# 6_CLCD.net
KiCad netlist of a schematic drawn in Altium Designer
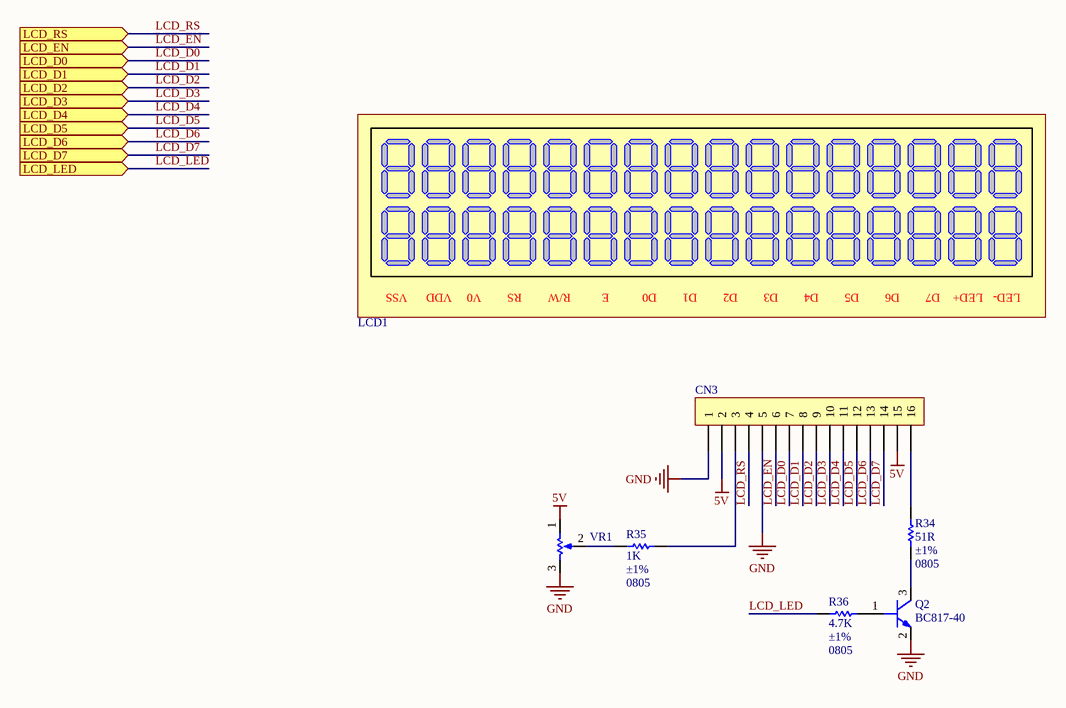
[diagram p0: 6.CLCD.SchDoc]

(export (version "E")
  (design (tool "Eeschema 10.0.6"))
  (components
    (comp (ref "CN3")
      (value "HDR_1X16")
      (footprint "HDRFV16W70P254_1X16_4064X254X1118P")
      (description "CONN HEADER FEMALE 16POS.1\" TIN")
      (fields
        (field (name "PART NUMBER") "SCON00136")
        (field (name "MANUFACTURER") "Sullins Connector Solutions")
      )
      (libsource (lib "ComponentDatabase") (part "HDR_1X16"))
    )
    (comp (ref "LCD1")
      (value "HD44780")
      (footprint "HD44780")
      (description "LCD MODULE 16X2 CHARACTER")
      (fields (field (name "PART NUMBER") "SOPT00201") (field (name "VOLTAGE") "5V"))
      (libsource (lib "ComponentDatabase") (part "HD44780"))
    )
    (comp (ref "Q2")
      (value "BC817-40")
      (footprint "SOT95P230X110-3N_SOT-23")
      (description "TRANS NPN 45V 0.5A SOT23")
      (fields (field (name "PART NUMBER") "STRANS00034") (field (name "MANUFACTURER") "NXP Semiconductors"))
      (libsource (lib "ComponentDatabase") (part "BC817"))
    )
    (comp (ref "R34")
      (value "51R")
      (footprint "RESC2013X65N_EIA0805")
      (description "RES SMD 51 OHM 1% 1/8W 0805")
      (fields
        (field (name "PART NUMBER") "SRES03010043")
        (field (name "TOLERANCE") "±1%")
        (field (name "PACKAGE / CASE") "0805")
        (field (name "MANUFACTURER") "Yageo")
      )
      (libsource (lib "ComponentDatabase") (part "RES"))
    )
    (comp (ref "R35")
      (value "1K")
      (footprint "RESC2013X65N_EIA0805")
      (description "RES SMD 1K OHM 1% 1/8W 0805")
      (fields
        (field (name "PART NUMBER") "SRES03010074")
        (field (name "TOLERANCE") "±1%")
        (field (name "PACKAGE / CASE") "0805")
        (field (name "MANUFACTURER") "Yageo")
      )
      (libsource (lib "ComponentDatabase") (part "RES"))
    )
    (comp (ref "R36")
      (value "4.7K")
      (footprint "RESC2013X65N_EIA0805")
      (description "RES SMD 4.7K OHM 1% 1/8W 0805")
      (fields
        (field (name "PART NUMBER") "SRES03010090")
        (field (name "TOLERANCE") "±1%")
        (field (name "PACKAGE / CASE") "0805")
        (field (name "MANUFACTURER") "Yageo")
      )
      (libsource (lib "ComponentDatabase") (part "RES"))
    )
    (comp (ref "VR1")
      (value "POT")
      (footprint "TRIMMER_SMD")
      (description "TRIMMER 10K OHM 0.15W SMD")
      (fields (field (name "PART NUMBER") "SPOT00047") (field (name "TOLERANCE") "±25%"))
      (libsource (lib "ComponentDatabase") (part "POT"))
    )
  )
  (nets
    (net (code "1") (name "/LCD_D0") (class "Default")
      (node (ref "CN3") (pin "7") (pinfunction "7_7") (pintype "passive"))
    )
    (net (code "2") (name "/LCD_D1") (class "Default")
      (node (ref "CN3") (pin "8") (pinfunction "8_8") (pintype "passive"))
    )
    (net (code "3") (name "/LCD_D2") (class "Default")
      (node (ref "CN3") (pin "9") (pinfunction "9_9") (pintype "passive"))
    )
    (net (code "4") (name "/LCD_D3") (class "Default")
      (node (ref "CN3") (pin "10") (pinfunction "10_10") (pintype "passive"))
    )
    (net (code "5") (name "/LCD_D4") (class "Default")
      (node (ref "CN3") (pin "11") (pinfunction "11_11") (pintype "passive"))
    )
    (net (code "6") (name "/LCD_D5") (class "Default")
      (node (ref "CN3") (pin "12") (pinfunction "12_12") (pintype "passive"))
    )
    (net (code "7") (name "/LCD_D6") (class "Default")
      (node (ref "CN3") (pin "13") (pinfunction "13_13") (pintype "passive"))
    )
    (net (code "8") (name "/LCD_D7") (class "Default")
      (node (ref "CN3") (pin "14") (pinfunction "14_14") (pintype "passive"))
    )
    (net (code "9") (name "/LCD_EN") (class "Default")
      (node (ref "CN3") (pin "6") (pinfunction "6_6") (pintype "passive"))
    )
    (net (code "10") (name "/LCD_LED") (class "Default")
      (node (ref "R36") (pin "2") (pinfunction "2_2") (pintype "passive"))
    )
    (net (code "11") (name "/LCD_RS") (class "Default")
      (node (ref "CN3") (pin "4") (pinfunction "4_4") (pintype "passive"))
    )
    (net (code "12") (name "5V") (class "Default")
      (node (ref "CN3") (pin "15") (pinfunction "15_15") (pintype "passive"))
      (node (ref "CN3") (pin "2") (pinfunction "2_2") (pintype "passive"))
      (node (ref "VR1") (pin "1") (pinfunction "TOP_1") (pintype "passive"))
    )
    (net (code "13") (name "GND") (class "Default")
      (node (ref "CN3") (pin "1") (pinfunction "1_1") (pintype "passive"))
      (node (ref "CN3") (pin "5") (pinfunction "5_5") (pintype "passive"))
      (node (ref "Q2") (pin "2") (pinfunction "E_2") (pintype "passive"))
      (node (ref "VR1") (pin "3") (pinfunction "BOT_3") (pintype "passive"))
    )
    (net (code "14") (name "Net-(CN3-Pad3)") (class "Default")
      (node (ref "CN3") (pin "3") (pinfunction "3_3") (pintype "passive"))
      (node (ref "R35") (pin "1") (pinfunction "1_1") (pintype "passive"))
    )
    (net (code "15") (name "Net-(CN3-Pad16)") (class "Default")
      (node (ref "CN3") (pin "16") (pinfunction "16_16") (pintype "passive"))
      (node (ref "R34") (pin "1") (pinfunction "1_1") (pintype "passive"))
    )
    (net (code "16") (name "Net-(Q2-B)") (class "Default")
      (node (ref "Q2") (pin "1") (pinfunction "B_1") (pintype "passive"))
      (node (ref "R36") (pin "1") (pinfunction "1_1") (pintype "passive"))
    )
    (net (code "17") (name "Net-(Q2-C)") (class "Default")
      (node (ref "Q2") (pin "3") (pinfunction "C_3") (pintype "passive"))
      (node (ref "R34") (pin "2") (pinfunction "2_2") (pintype "passive"))
    )
    (net (code "18") (name "Net-(VR1-TAP)") (class "Default")
      (node (ref "R35") (pin "2") (pinfunction "2_2") (pintype "passive"))
      (node (ref "VR1") (pin "2") (pinfunction "TAP_2") (pintype "passive"))
    )
  )
)
